# 03_POWER.net
KiCad netlist of a schematic drawn in Altium Designer
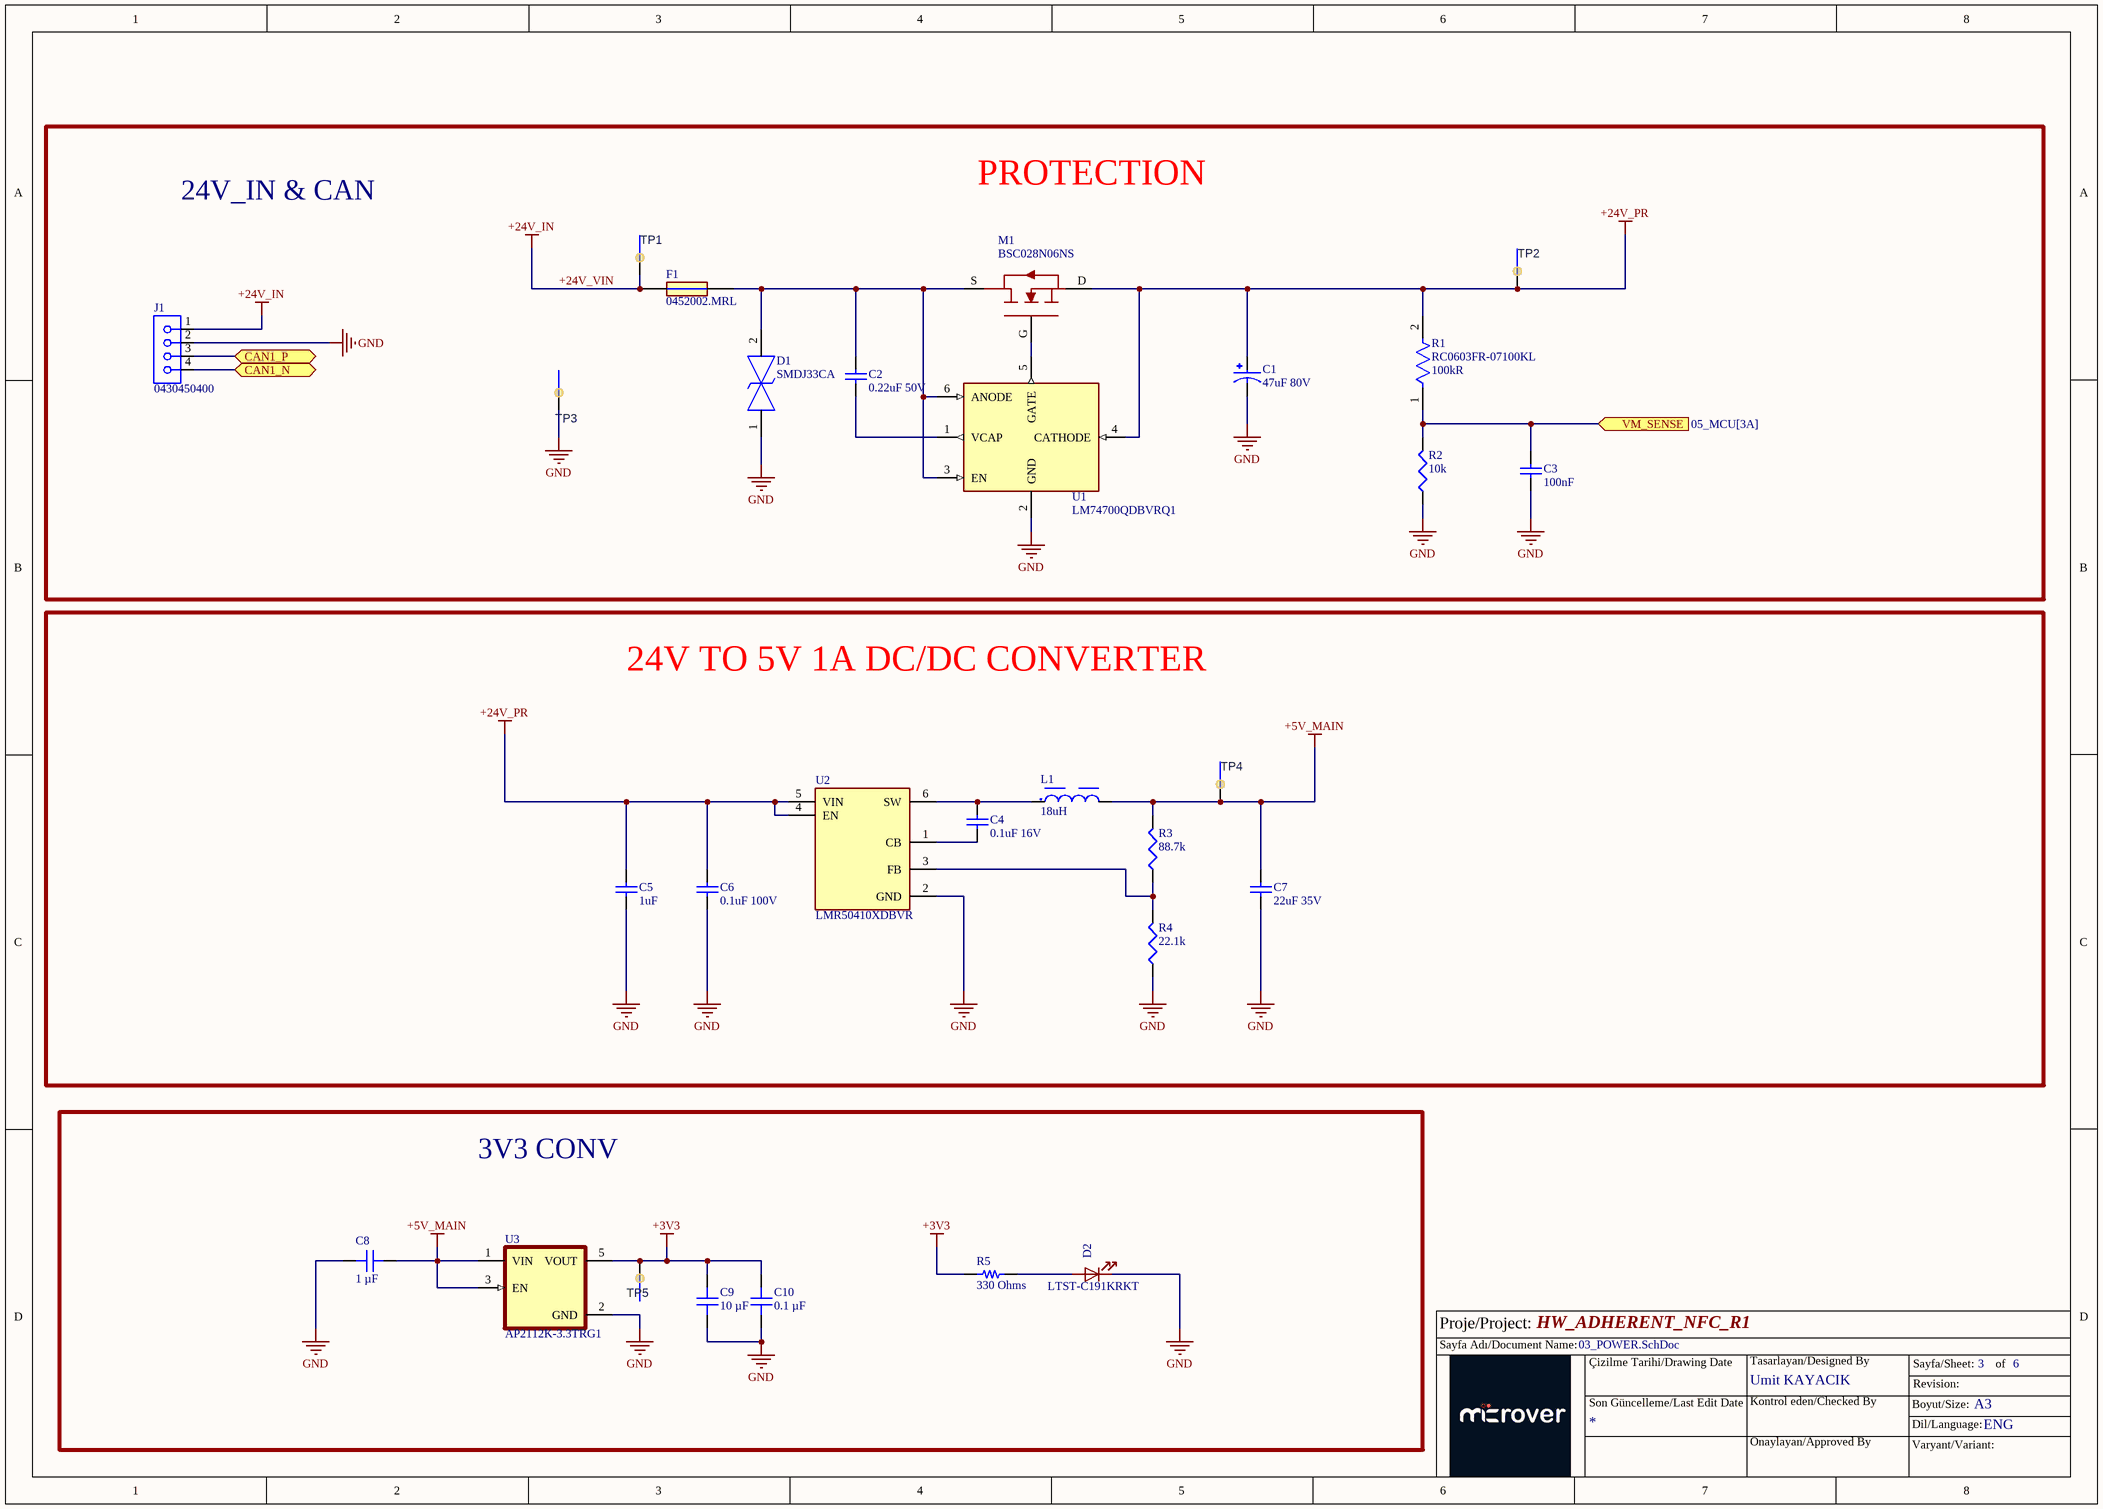
[diagram p0: 03_POWER.SchDoc]

(export (version "E")
  (design (tool "Eeschema 10.0.6"))
  (components
    (comp (ref "C1")
      (value "47uF 80V")
      (footprint "CAP_EEEFK1K470P")
      (description "47 µF 80 V Aluminum Electrolytic Capacitors Radial, Can - SMD 2000 Hrs @ 105°C")
      (fields (field (name "MANUFACTURER") "Panasonic Industry"))
      (libsource (lib "HW_ADHERENT_NFC_R1_L1") (part "EEE-FK1K470P"))
    )
    (comp (ref "C2")
      (value "0.22uF 50V")
      (footprint "SMC0603")
      (description "0.22 µF ±10% 50V Ceramic Capacitor X7R 0603 (1608 Metric)")
      (fields
        (field (name "MANUFACTURER PART NUMBER") "GCM188R71H224KA64D")
        (field (name "Comment") "CAP CER 0.22UF 50V X7R 0603")
      )
      (libsource (lib "HW_ADHERENT_LANECTRL_R1") (part "CAP0603_0.22UF_50V"))
    )
    (comp (ref "C3")
      (value "100nF")
      (footprint "CAP0603")
      (description "0.1 µF ±10% 50V Ceramic Capacitor X7R 0603 (1608 Metric)")
      (fields
        (field (name "MANUFACTURER PART NUMBER") "CL10B104KA8NNNC")
        (field (name "LCSC PART NUMBER") "C1590")
      )
      (libsource (lib "HW_ADHERENT_LANECTRL_R1") (part "CAP0603_100nF"))
    )
    (comp (ref "C4")
      (value "0.1uF 16V")
      (footprint "CAP0603")
      (description "0.1 µF ±20% 16V Ceramic Capacitor X7R 0603 (1608 Metric)")
      (libsource (lib "HW_ADHERENT_LANECTRL_R1") (part "C0603C104M4RACTU"))
    )
    (comp (ref "C5")
      (value "1uF")
      (footprint "CAP0603")
      (description "CAP CER 1UF 50V X5R 0603")
      (fields (field (name "MANUFACTURER") "Taiyo Yuden"))
      (libsource (lib "HW_ADHERENT_LANECTRL_R1") (part "MSASU168SB5105MTNA01"))
    )
    (comp (ref "C6")
      (value "0.1uF 100V")
      (footprint "CAP0603")
      (description "CAP CER 0.1UF 100V X7R 0603")
      (libsource (lib "HW_ADHERENT_LANECTRL_R1") (part "GRM188R72A104KA35D"))
    )
    (comp (ref "C7")
      (value "22uF 35V")
      (footprint "CAP1206")
      (description "22 µF ±20% 35V Ceramic Capacitor X5R 1206 (3216 Metric)")
      (fields (field (name "MANUFACTURER PART NUMBER") "C3216X5R1V226M160AC"))
      (libsource (lib "HW_ADHERENT_LANECTRL_R1") (part "CAP1206_22uF_35V"))
    )
    (comp (ref "C8")
      (value "1 µF")
      (footprint "CAP 0603_1608")
      (description "CAP0603 X7R 1UF 10% 25V")
      (fields
        (field (name "PART NUMBER") "GMC10X7R105K25NT")
        (field (name "CAPACITANCE") "1 µF")
        (field (name "MANUFACTURER") "Cal-Chip Electronics, Inc.")
      )
      (libsource (lib "Celestial Altium Library - altium_library") (part "Capacitor"))
    )
    (comp (ref "C9")
      (value "10 µF")
      (footprint "CAP 0805_2012")
      (description "CAP CER 10UF 50V X5R 0805")
      (fields
        (field (name "PART NUMBER") "GRM21BR61H106KE43L")
        (field (name "CAPACITANCE") "10 µF")
        (field (name "MANUFACTURER") "Murata Electronics")
      )
      (libsource (lib "Celestial Altium Library - altium_library") (part "Capacitor"))
    )
    (comp (ref "C10")
      (value "GCM188R71H104KA57J")
      (footprint "CAP 0603_1608")
      (description "CAP CER 0.1UF 50V X7R 0603")
      (fields
        (field (name "CAPACITANCE") "0.1 µF")
        (field (name "MANUFACTURER") "Murata Electronics")
        (field (name "TOLERANCE") "±10%")
      )
      (libsource (lib "Celestial Altium Library - altium_library") (part "Capacitor"))
    )
    (comp (ref "D1")
      (value "SMDJ33CA")
      (footprint "DIONM7959X262N")
      (description "53.3V Clamp 56.3A Ipp Tvs Diode Surface Mount DO-214AB (SMCJ)")
      (fields (field (name "MANUFACTURER") "Littelfuse Inc."))
      (libsource (lib "HW_ADHERENT_NFC_R1_L1") (part "SMDJ33CA"))
    )
    (comp (ref "D2")
      (value "LTST-C191KRKT")
      (footprint "LED0603")
      (description "LED RED CLEAR SMD")
      (fields (field (name "MANUFACTURER") "Lite-On Inc."))
      (libsource (lib "HW_ADHERENT_NFC_R1_L3") (part "LED_1"))
    )
    (comp (ref "F1")
      (value "0452002.MRL")
      (footprint "FUSC6127X294N")
      (description "2 A 125 V 125 V Fuse Board Mount (Cartridge Style Excluded) Surface Mount 2-SMD, Square End Block")
      (fields (field (name "MANUFACTURER") "Littelfuse Inc."))
      (libsource (lib "HW_ADHERENT_NFC_R1_L1") (part "0452002.MRL"))
    )
    (comp (ref "J1")
      (value "0430450400")
      (footprint "CONN_SD-43045-001_04_MOL")
      (description "Connector Header Through Hole, Right Angle 4 position 0.118\" (3.00mm)")
      (libsource (lib "HW_ADHERENT_NFC_R1_L1") (part "0430450400"))
    )
    (comp (ref "L1")
      (value "18uH")
      (footprint "WE-LQS_6045")
      (description "18 µH Semi-Shielded Drum Core, Wirewound Inductor 2.2 A 81mOhm Nonstandard")
      (libsource (lib "HW_ADHERENT_LANECTRL_R1") (part "74404064180"))
    )
    (comp (ref "M1")
      (value "BSC028N06NS")
      (footprint "BSC028N06NS")
      (description "MOSFET'ler N-Ch 60V 100A TDSON-8 OptiMOS 3")
      (libsource (lib "HW_ADHERENT_LANECTRL_R1") (part "BSC028N06NS"))
    )
    (comp (ref "R1")
      (value "RC0603FR-07100KL")
      (footprint "FP-RC0603-0_55-MFG")
      (description "RES SMD 100K OHM 1% 1/10W 0603")
      (fields (field (name "RESISTANCE") "100kR") (field (name "TOLERANCE") "1%"))
      (libsource (lib "HW_ADHERENT_LANECTRL_R1") (part "CMP-2100-03662-2"))
    )
    (comp (ref "R2")
      (value "10k")
      (footprint "RES0603")
      (description "10 kOhms ±1% 0.125W, 1/8W Chip Resistor 0603 (1608 Metric) Anti-Sulfur Thin Film")
      (fields
        (field (name "MANUFACTURER PART NUMBER") "RNCP0603FTD10K0")
        (field (name "LCSC PART NUMBER") "C161803")
      )
      (libsource (lib "HW_ADHERENT_LANECTRL_R1") (part "RES0603_10K_%1_1"))
    )
    (comp (ref "R3")
      (value "88.7k")
      (footprint "RES0603")
      (description "88.7 kOhms ±1% 0.125W, 1/8W Chip Resistor 0603 (1608 Metric) Automotive AEC-Q200 Thick Film")
      (libsource (lib "HW_ADHERENT_LANECTRL_R1") (part "CRCW060388K7FKEA"))
    )
    (comp (ref "R4")
      (value "22.1k")
      (footprint "RES0603")
      (description "22.1 kOhms ±1% 0.1W, 1/10W Chip Resistor 0603 (1608 Metric) Moisture Resistant Thick Film")
      (libsource (lib "HW_ADHERENT_LANECTRL_R1") (part "RC0603FR-0722K1L"))
    )
    (comp (ref "R5")
      (value "330 Ohms")
      (footprint "RES 0603_1608")
      (description "RES SMD 330 OHM 1% 1/5W 0603")
      (fields
        (field (name "PART NUMBER") "CRGH0603F330R")
        (field (name "MANUFACTURER") "TE Connectivity Passive Product")
      )
      (libsource (lib "HW_ADHERENT_NFC_R1_L3") (part "CRGH0603F330R"))
    )
    (comp (ref "TP1")
      (value "Testpoint")
      (footprint "SMD_1P5mm")
      (description "Testpoint / 2.0mm Pad / TP200")
      (libsource (lib "HW_ADHERENT_NFC_R1_L3") (part "Testpoint / 1.0mm Pad / TP100"))
    )
    (comp (ref "TP2")
      (value "Testpoint")
      (footprint "SMD_1P5mm")
      (description "Testpoint / 2.0mm Pad / TP200")
      (libsource (lib "HW_ADHERENT_NFC_R1_L3") (part "Testpoint / 1.0mm Pad / TP100"))
    )
    (comp (ref "TP3")
      (value "Testpoint")
      (footprint "SMD_1P5mm")
      (description "Testpoint / 2.0mm Pad / TP200")
      (libsource (lib "HW_ADHERENT_NFC_R1_L3") (part "Testpoint / 1.0mm Pad / TP100"))
    )
    (comp (ref "TP4")
      (value "Testpoint")
      (footprint "SMD_1P5mm")
      (description "Testpoint / 2.0mm Pad / TP200")
      (libsource (lib "HW_ADHERENT_NFC_R1_L3") (part "Testpoint / 1.0mm Pad / TP100"))
    )
    (comp (ref "TP5")
      (value "Testpoint")
      (footprint "SMD_1P5mm")
      (description "Testpoint / 2.0mm Pad / TP200")
      (libsource (lib "") (part "Testpoint / 1.0mm Pad / TP100_1"))
    )
    (comp (ref "U1")
      (value "LM74700QDBVRQ1")
      (footprint "SOT95P280X145-6N/LM74700QDBVRQ1")
      (description "OR Controller N+1 ORing Controller N-Channel 1:1 SOT-23-6")
      (libsource (lib "HW_ADHERENT_NFC_R1_L3") (part "LM74700QDBVRQ1"))
    )
    (comp (ref "U2")
      (value "LMR50410XDBVR")
      (footprint "SOT95P280X145-6N/")
      (description "Buck Switching Regulator IC Positive Adjustable 1V 1 Output 1A SOT-23-6")
      (libsource (lib "HW_ADHERENT_LANECTRL_R1") (part "LMR50410XDBVR"))
    )
    (comp (ref "U3")
      (value "AP2112K-3.3TRG1")
      (footprint "SOT95P285X140-5N")
      (description "Linear Voltage Regulator IC Positive Fixed 1 Output 600mA SOT-25")
      (fields (field (name "MF") "Diodes Inc."))
      (libsource (lib "HW_PEINFO_RF_RECEIVER_R1") (part "AP2112K-3.3TRG1"))
    )
  )
  (nets
    (net (code "1") (name "+3V3") (class "Default")
      (node (ref "C10") (pin "2") (pinfunction "2_2") (pintype "passive"))
      (node (ref "C9") (pin "2") (pinfunction "2_2") (pintype "passive"))
      (node (ref "R5") (pin "1") (pinfunction "1_1") (pintype "passive"))
      (node (ref "TP5") (pin "1") (pinfunction "TP_1") (pintype "passive"))
      (node (ref "U3") (pin "5") (pinfunction "VOUT_5") (pintype "power_in"))
    )
    (net (code "2") (name "+5V_MAIN") (class "Default")
      (node (ref "C7") (pin "2") (pinfunction "2_2") (pintype "passive"))
      (node (ref "C8") (pin "2") (pinfunction "2_2") (pintype "passive"))
      (node (ref "L1") (pin "2") (pinfunction "2_2") (pintype "passive"))
      (node (ref "R3") (pin "2") (pinfunction "2_2") (pintype "passive"))
      (node (ref "TP4") (pin "1") (pinfunction "TP_1") (pintype "passive"))
      (node (ref "U3") (pin "1") (pinfunction "VIN_1") (pintype "power_in"))
      (node (ref "U3") (pin "3") (pinfunction "EN_3") (pintype "input"))
    )
    (net (code "3") (name "+24V_IN") (class "Default")
      (node (ref "F1") (pin "1") (pinfunction "1_1") (pintype "passive"))
      (node (ref "J1") (pin "1") (pinfunction "1_1") (pintype "passive"))
      (node (ref "TP1") (pin "1") (pinfunction "TP_1") (pintype "passive"))
    )
    (net (code "4") (name "+24V_PR") (class "Default")
      (node (ref "C1") (pin "1") (pinfunction "1_1") (pintype "passive"))
      (node (ref "C5") (pin "2") (pinfunction "2_2") (pintype "passive"))
      (node (ref "C6") (pin "2") (pinfunction "2_2") (pintype "passive"))
      (node (ref "M1") (pin "D") (pinfunction "D_D") (pintype "passive"))
      (node (ref "R1") (pin "2") (pinfunction "2_2") (pintype "passive"))
      (node (ref "TP2") (pin "1") (pinfunction "TP_1") (pintype "passive"))
      (node (ref "U1") (pin "4") (pinfunction "CATHODE_4") (pintype "input"))
      (node (ref "U2") (pin "4") (pinfunction "EN_4") (pintype "passive"))
      (node (ref "U2") (pin "5") (pinfunction "VIN_5") (pintype "power_in"))
    )
    (net (code "5") (name "/CAN1_N") (class "Default")
      (node (ref "J1") (pin "4") (pinfunction "4_4") (pintype "passive"))
    )
    (net (code "6") (name "/CAN1_P") (class "Default")
      (node (ref "J1") (pin "3") (pinfunction "3_3") (pintype "passive"))
    )
    (net (code "7") (name "/VM_SENSE") (class "Default")
      (node (ref "C3") (pin "2") (pinfunction "2_2") (pintype "passive"))
      (node (ref "R1") (pin "1") (pinfunction "1_1") (pintype "passive"))
      (node (ref "R2") (pin "2") (pinfunction "2_2") (pintype "passive"))
    )
    (net (code "8") (name "GND") (class "Default")
      (node (ref "C1") (pin "2") (pinfunction "2_2") (pintype "passive"))
      (node (ref "C10") (pin "1") (pinfunction "1_1") (pintype "passive"))
      (node (ref "C3") (pin "1") (pinfunction "1_1") (pintype "passive"))
      (node (ref "C5") (pin "1") (pinfunction "1_1") (pintype "passive"))
      (node (ref "C6") (pin "1") (pinfunction "1_1") (pintype "passive"))
      (node (ref "C7") (pin "1") (pinfunction "1_1") (pintype "passive"))
      (node (ref "C8") (pin "1") (pinfunction "1_1") (pintype "passive"))
      (node (ref "C9") (pin "1") (pinfunction "1_1") (pintype "passive"))
      (node (ref "D1") (pin "1") (pinfunction "1_1") (pintype "passive"))
      (node (ref "D2") (pin "2") (pinfunction "K_2") (pintype "passive"))
      (node (ref "J1") (pin "2") (pinfunction "2_2") (pintype "passive"))
      (node (ref "R2") (pin "1") (pinfunction "1_1") (pintype "passive"))
      (node (ref "R4") (pin "1") (pinfunction "1_1") (pintype "passive"))
      (node (ref "TP3") (pin "1") (pinfunction "TP_1") (pintype "passive"))
      (node (ref "U1") (pin "2") (pinfunction "GND_2") (pintype "power_in"))
      (node (ref "U2") (pin "2") (pinfunction "GND_2") (pintype "passive"))
      (node (ref "U3") (pin "2") (pinfunction "GND_2") (pintype "power_in"))
    )
    (net (code "9") (name "Net-(D2-A)") (class "Default")
      (node (ref "D2") (pin "1") (pinfunction "A_1") (pintype "passive"))
      (node (ref "R5") (pin "2") (pinfunction "2_2") (pintype "passive"))
    )
    (net (code "10") (name "Net-(U1-ANODE)") (class "Default")
      (node (ref "C2") (pin "2") (pinfunction "2_2") (pintype "passive"))
      (node (ref "D1") (pin "2") (pinfunction "2_2") (pintype "passive"))
      (node (ref "F1") (pin "2") (pinfunction "2_2") (pintype "passive"))
      (node (ref "M1") (pin "S") (pinfunction "S_S") (pintype "passive"))
      (node (ref "U1") (pin "3") (pinfunction "EN_3") (pintype "input"))
      (node (ref "U1") (pin "6") (pinfunction "ANODE_6") (pintype "input"))
    )
    (net (code "11") (name "Net-(U1-GATE)") (class "Default")
      (node (ref "M1") (pin "G") (pinfunction "G_G") (pintype "passive"))
      (node (ref "U1") (pin "5") (pinfunction "GATE_5") (pintype "output"))
    )
    (net (code "12") (name "Net-(U1-VCAP)") (class "Default")
      (node (ref "C2") (pin "1") (pinfunction "1_1") (pintype "passive"))
      (node (ref "U1") (pin "1") (pinfunction "VCAP_1") (pintype "output"))
    )
    (net (code "13") (name "Net-(U2-CB)") (class "Default")
      (node (ref "C4") (pin "1") (pinfunction "1_1") (pintype "passive"))
      (node (ref "U2") (pin "1") (pinfunction "CB_1") (pintype "passive"))
    )
    (net (code "14") (name "Net-(U2-FB)") (class "Default")
      (node (ref "R3") (pin "1") (pinfunction "1_1") (pintype "passive"))
      (node (ref "R4") (pin "2") (pinfunction "2_2") (pintype "passive"))
      (node (ref "U2") (pin "3") (pinfunction "FB_3") (pintype "passive"))
    )
    (net (code "15") (name "Net-(U2-SW)") (class "Default")
      (node (ref "C4") (pin "2") (pinfunction "2_2") (pintype "passive"))
      (node (ref "L1") (pin "1") (pinfunction "1_1") (pintype "passive"))
      (node (ref "U2") (pin "6") (pinfunction "SW_6") (pintype "passive"))
    )
  )
)
